# temp_sensing.net
KiCad netlist of a schematic drawn in EAGLE
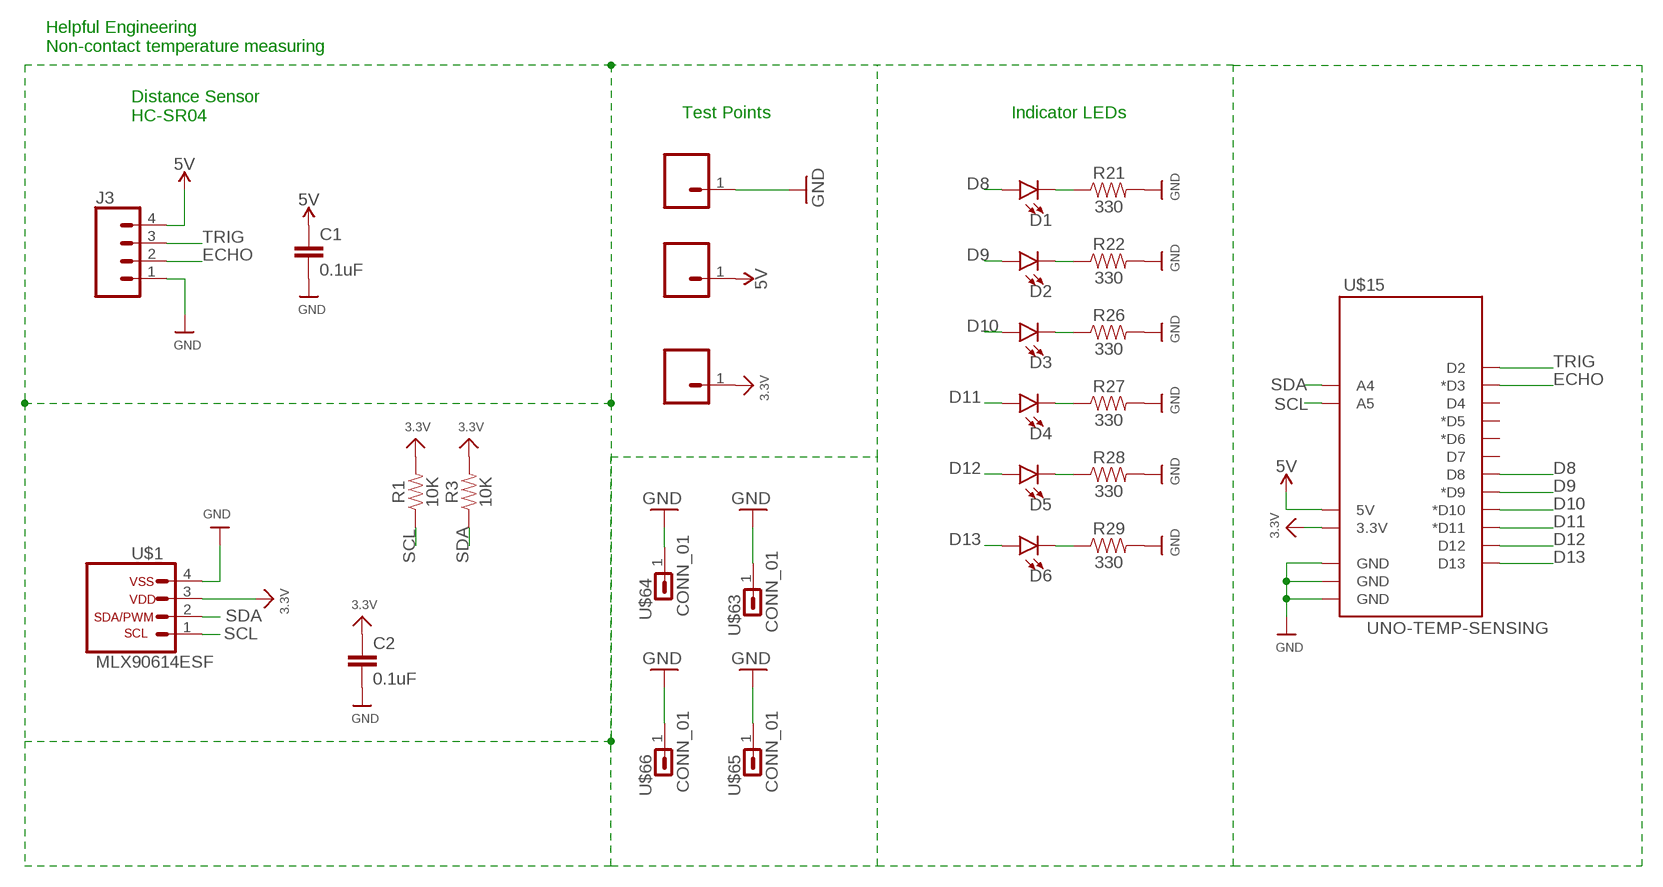
[diagram p0: schematic, sheet 1]

(export (version "E")
  (design (tool "Eeschema 10.0.6"))
  (components
    (comp (ref "C1")
      (value "0.1uF")
      (footprint "eagle-import:CAP-PTH-SMALL-KIT")
      (libsource (lib "eagle-import") (part "0.1UF-KIT-EZ-50V-20%"))
    )
    (comp (ref "C2")
      (value "0.1uF")
      (footprint "eagle-import:CAP-PTH-SMALL-KIT")
      (libsource (lib "eagle-import") (part "0.1UF-KIT-EZ-50V-20%"))
    )
    (comp (ref "D1")
      (value "LED10MM")
      (footprint "eagle-import:LED_10MM")
      (libsource (lib "eagle-import") (part "LED10MM"))
    )
    (comp (ref "D2")
      (value "LED10MM")
      (footprint "eagle-import:LED_10MM")
      (libsource (lib "eagle-import") (part "LED10MM"))
    )
    (comp (ref "D3")
      (value "LED10MM")
      (footprint "eagle-import:LED_10MM")
      (libsource (lib "eagle-import") (part "LED10MM"))
    )
    (comp (ref "D4")
      (value "LED10MM")
      (footprint "eagle-import:LED_10MM")
      (libsource (lib "eagle-import") (part "LED10MM"))
    )
    (comp (ref "D5")
      (value "LED10MM")
      (footprint "eagle-import:LED_10MM")
      (libsource (lib "eagle-import") (part "LED10MM"))
    )
    (comp (ref "D6")
      (value "LED10MM")
      (footprint "eagle-import:LED_10MM")
      (libsource (lib "eagle-import") (part "LED10MM"))
    )
    (comp (ref "J3")
      (value "CONN_04PTH")
      (footprint "eagle-import:1X04")
      (libsource (lib "eagle-import") (part "CONN_04PTH"))
    )
    (comp (ref "R1")
      (value "10K")
      (footprint "eagle-import:AXIAL-0.3")
      (libsource (lib "eagle-import") (part "330OHM-HORIZ-1/10W-5%"))
    )
    (comp (ref "R3")
      (value "10K")
      (footprint "eagle-import:AXIAL-0.3")
      (libsource (lib "eagle-import") (part "330OHM-HORIZ-1/10W-5%"))
    )
    (comp (ref "R21")
      (value "330")
      (footprint "eagle-import:AXIAL-0.3")
      (libsource (lib "eagle-import") (part "330OHM-HORIZ-1/10W-5%"))
    )
    (comp (ref "R22")
      (value "330")
      (footprint "eagle-import:AXIAL-0.3")
      (libsource (lib "eagle-import") (part "330OHM-HORIZ-1/10W-5%"))
    )
    (comp (ref "R26")
      (value "330")
      (footprint "eagle-import:AXIAL-0.3")
      (libsource (lib "eagle-import") (part "330OHM-HORIZ-1/10W-5%"))
    )
    (comp (ref "R27")
      (value "330")
      (footprint "eagle-import:AXIAL-0.3")
      (libsource (lib "eagle-import") (part "330OHM-HORIZ-1/10W-5%"))
    )
    (comp (ref "R28")
      (value "330")
      (footprint "eagle-import:AXIAL-0.3")
      (libsource (lib "eagle-import") (part "330OHM-HORIZ-1/10W-5%"))
    )
    (comp (ref "R29")
      (value "330")
      (footprint "eagle-import:AXIAL-0.3")
      (libsource (lib "eagle-import") (part "330OHM-HORIZ-1/10W-5%"))
    )
    (comp (ref "U$1")
      (value "MLX90614ESF")
      (footprint "eagle-import:MLX90614XCI")
      (libsource (lib "eagle-import") (part "MLX90614ESF"))
    )
    (comp (ref "U$15")
      (value "UNO-TEMP-SENSING")
      (footprint "eagle-import:UNO_FOOTRPINT")
      (libsource (lib "eagle-import") (part "UNO-TEMP-SENSING"))
    )
    (comp (ref "U$20")
      (value "CONN_0138MILL")
      (footprint "eagle-import:1X01-40MILL")
      (libsource (lib "eagle-import") (part "th_libraries3_CONN_0138MILL"))
    )
    (comp (ref "U$31")
      (value "CONN_0138MILL")
      (footprint "eagle-import:1X01-40MILL")
      (libsource (lib "eagle-import") (part "th_libraries3_CONN_0138MILL"))
    )
    (comp (ref "U$59")
      (value "CONN_0138MILL")
      (footprint "eagle-import:1X01-40MILL")
      (libsource (lib "eagle-import") (part "th_libraries3_CONN_0138MILL"))
    )
    (comp (ref "U$63")
      (value "CONN_01")
      (footprint "eagle-import:1X01-#6_MACHINE")
      (libsource (lib "eagle-import") (part "CONN_01"))
    )
    (comp (ref "U$64")
      (value "CONN_01")
      (footprint "eagle-import:1X01-#6_MACHINE")
      (libsource (lib "eagle-import") (part "CONN_01"))
    )
    (comp (ref "U$65")
      (value "CONN_01")
      (footprint "eagle-import:1X01-#6_MACHINE")
      (libsource (lib "eagle-import") (part "CONN_01"))
    )
    (comp (ref "U$66")
      (value "CONN_01")
      (footprint "eagle-import:1X01-#6_MACHINE")
      (libsource (lib "eagle-import") (part "CONN_01"))
    )
  )
  (nets
    (net (code "1") (name "/D8") (class "Default")
      (node (ref "D1") (pin "A") (pinfunction "A_A") (pintype "passive"))
      (node (ref "U$15") (pin "D8") (pinfunction "D8_D8") (pintype "bidirectional"))
    )
    (net (code "2") (name "/D9") (class "Default")
      (node (ref "D2") (pin "A") (pinfunction "A_A") (pintype "passive"))
      (node (ref "U$15") (pin "D9") (pinfunction "*D9_D9") (pintype "bidirectional"))
    )
    (net (code "3") (name "/D10") (class "Default")
      (node (ref "D3") (pin "A") (pinfunction "A_A") (pintype "passive"))
      (node (ref "U$15") (pin "D10") (pinfunction "*D10_D10") (pintype "bidirectional"))
    )
    (net (code "4") (name "/D11") (class "Default")
      (node (ref "D4") (pin "A") (pinfunction "A_A") (pintype "passive"))
      (node (ref "U$15") (pin "D11") (pinfunction "*D11_D11") (pintype "bidirectional"))
    )
    (net (code "5") (name "/D12") (class "Default")
      (node (ref "D5") (pin "A") (pinfunction "A_A") (pintype "passive"))
      (node (ref "U$15") (pin "D12") (pinfunction "D12_D12") (pintype "bidirectional"))
    )
    (net (code "6") (name "/D13") (class "Default")
      (node (ref "D6") (pin "A") (pinfunction "A_A") (pintype "passive"))
      (node (ref "U$15") (pin "D13") (pinfunction "D13_D13") (pintype "bidirectional"))
    )
    (net (code "7") (name "/ECHO") (class "Default")
      (node (ref "J3") (pin "2") (pinfunction "2_2") (pintype "passive"))
      (node (ref "U$15") (pin "D3") (pinfunction "*D3_D3") (pintype "bidirectional"))
    )
    (net (code "8") (name "/SCL") (class "Default")
      (node (ref "R1") (pin "P$1") (pinfunction "1_P$1") (pintype "passive"))
      (node (ref "U$1") (pin "1") (pinfunction "1_1") (pintype "passive"))
      (node (ref "U$15") (pin "A5") (pinfunction "A5_A5") (pintype "bidirectional"))
    )
    (net (code "9") (name "/SDA") (class "Default")
      (node (ref "R3") (pin "P$1") (pinfunction "1_P$1") (pintype "passive"))
      (node (ref "U$1") (pin "2") (pinfunction "2_2") (pintype "passive"))
      (node (ref "U$15") (pin "A4") (pinfunction "A4_A4") (pintype "bidirectional"))
    )
    (net (code "10") (name "/TRIG") (class "Default")
      (node (ref "J3") (pin "3") (pinfunction "3_3") (pintype "passive"))
      (node (ref "U$15") (pin "D2") (pinfunction "D2_D2") (pintype "bidirectional"))
    )
    (net (code "11") (name "3.3V") (class "Default")
      (node (ref "C2") (pin "1") (pinfunction "1_1") (pintype "passive"))
      (node (ref "R1") (pin "P$2") (pinfunction "2_P$2") (pintype "passive"))
      (node (ref "R3") (pin "P$2") (pinfunction "2_P$2") (pintype "passive"))
      (node (ref "U$1") (pin "3") (pinfunction "3_3") (pintype "passive"))
      (node (ref "U$15") (pin "3.3V") (pinfunction "3.3V_3.3V") (pintype "bidirectional"))
      (node (ref "U$20") (pin "1") (pinfunction "1_1") (pintype "passive"))
    )
    (net (code "12") (name "5V") (class "Default")
      (node (ref "C1") (pin "1") (pinfunction "1_1") (pintype "passive"))
      (node (ref "J3") (pin "4") (pinfunction "4_4") (pintype "passive"))
      (node (ref "U$15") (pin "5V") (pinfunction "5V_5V") (pintype "bidirectional"))
      (node (ref "U$59") (pin "1") (pinfunction "1_1") (pintype "passive"))
    )
    (net (code "13") (name "GND") (class "Default")
      (node (ref "C1") (pin "2") (pinfunction "2_2") (pintype "passive"))
      (node (ref "C2") (pin "2") (pinfunction "2_2") (pintype "passive"))
      (node (ref "J3") (pin "1") (pinfunction "1_1") (pintype "passive"))
      (node (ref "R21") (pin "P$2") (pinfunction "2_P$2") (pintype "passive"))
      (node (ref "R22") (pin "P$2") (pinfunction "2_P$2") (pintype "passive"))
      (node (ref "R26") (pin "P$2") (pinfunction "2_P$2") (pintype "passive"))
      (node (ref "R27") (pin "P$2") (pinfunction "2_P$2") (pintype "passive"))
      (node (ref "R28") (pin "P$2") (pinfunction "2_P$2") (pintype "passive"))
      (node (ref "R29") (pin "P$2") (pinfunction "2_P$2") (pintype "passive"))
      (node (ref "U$1") (pin "4") (pinfunction "4_4") (pintype "passive"))
      (node (ref "U$15") (pin "GND@0") (pinfunction "GND_GND@0") (pintype "bidirectional"))
      (node (ref "U$15") (pin "GND@1") (pinfunction "GND_GND@1") (pintype "bidirectional"))
      (node (ref "U$15") (pin "GND@2") (pinfunction "GND_GND@2") (pintype "bidirectional"))
      (node (ref "U$31") (pin "1") (pinfunction "1_1") (pintype "passive"))
      (node (ref "U$63") (pin "1") (pinfunction "1_1") (pintype "passive"))
      (node (ref "U$64") (pin "1") (pinfunction "1_1") (pintype "passive"))
      (node (ref "U$65") (pin "1") (pinfunction "1_1") (pintype "passive"))
      (node (ref "U$66") (pin "1") (pinfunction "1_1") (pintype "passive"))
    )
    (net (code "14") (name "Net-(R21-1)") (class "Default")
      (node (ref "D1") (pin "C") (pinfunction "C_C") (pintype "passive"))
      (node (ref "R21") (pin "P$1") (pinfunction "1_P$1") (pintype "passive"))
    )
    (net (code "15") (name "Net-(R22-1)") (class "Default")
      (node (ref "D2") (pin "C") (pinfunction "C_C") (pintype "passive"))
      (node (ref "R22") (pin "P$1") (pinfunction "1_P$1") (pintype "passive"))
    )
    (net (code "16") (name "Net-(R26-1)") (class "Default")
      (node (ref "D3") (pin "C") (pinfunction "C_C") (pintype "passive"))
      (node (ref "R26") (pin "P$1") (pinfunction "1_P$1") (pintype "passive"))
    )
    (net (code "17") (name "Net-(R27-1)") (class "Default")
      (node (ref "D4") (pin "C") (pinfunction "C_C") (pintype "passive"))
      (node (ref "R27") (pin "P$1") (pinfunction "1_P$1") (pintype "passive"))
    )
    (net (code "18") (name "Net-(R28-1)") (class "Default")
      (node (ref "D5") (pin "C") (pinfunction "C_C") (pintype "passive"))
      (node (ref "R28") (pin "P$1") (pinfunction "1_P$1") (pintype "passive"))
    )
    (net (code "19") (name "Net-(R29-1)") (class "Default")
      (node (ref "D6") (pin "C") (pinfunction "C_C") (pintype "passive"))
      (node (ref "R29") (pin "P$1") (pinfunction "1_P$1") (pintype "passive"))
    )
    (net (code "20") (name "unconnected-(U$15-*D5-PadD5)") (class "Default")
      (node (ref "U$15") (pin "D5") (pinfunction "*D5_D5") (pintype "bidirectional"))
    )
    (net (code "21") (name "unconnected-(U$15-*D6-PadD6)") (class "Default")
      (node (ref "U$15") (pin "D6") (pinfunction "*D6_D6") (pintype "bidirectional"))
    )
    (net (code "22") (name "unconnected-(U$15-PadD4)") (class "Default")
      (node (ref "U$15") (pin "D4") (pinfunction "D4_D4") (pintype "bidirectional"))
    )
    (net (code "23") (name "unconnected-(U$15-PadD7)") (class "Default")
      (node (ref "U$15") (pin "D7") (pinfunction "D7_D7") (pintype "bidirectional"))
    )
  )
)
